# Breakout.net
KiCad netlist of a schematic drawn in EAGLE
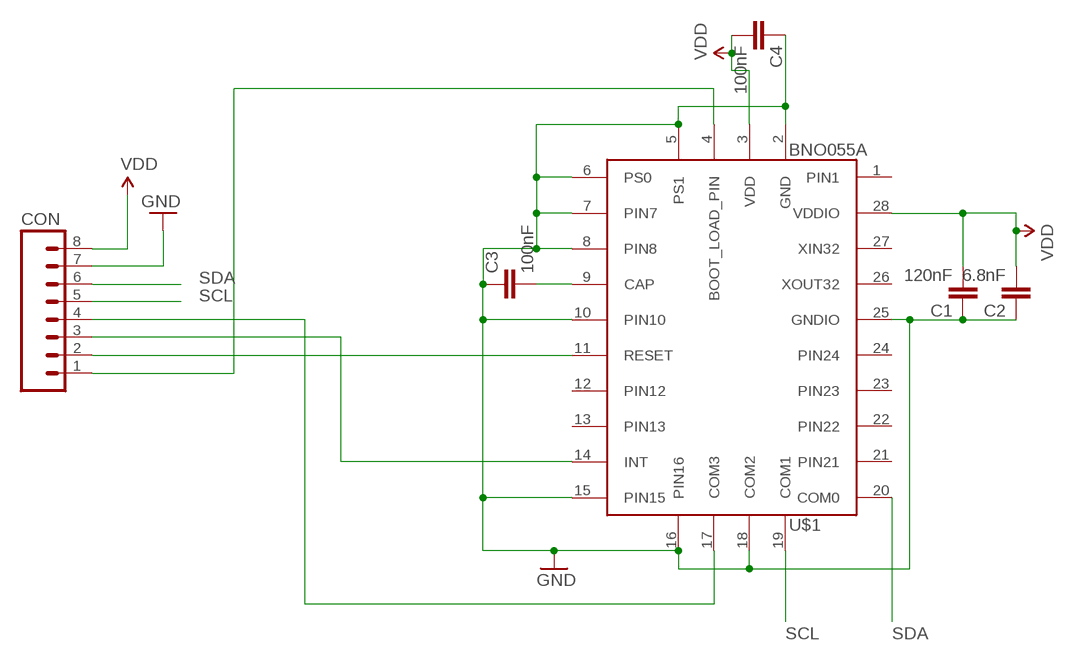
[diagram p0: schematic, sheet 1]

(export (version "E")
  (design (tool "Eeschema 10.0.6"))
  (components
    (comp (ref "C1")
      (value "120nF")
      (footprint "eagle-import:1206")
      (libsource (lib "eagle-import") (part "CAP1206"))
    )
    (comp (ref "C2")
      (value "6.8nF")
      (footprint "eagle-import:1206")
      (libsource (lib "eagle-import") (part "CAP1206"))
    )
    (comp (ref "C3")
      (value "100nF")
      (footprint "eagle-import:1206")
      (libsource (lib "eagle-import") (part "CAP1206"))
    )
    (comp (ref "C4")
      (value "100nF")
      (footprint "eagle-import:1206")
      (libsource (lib "eagle-import") (part "CAP1206"))
    )
    (comp (ref "CON")
      (value "M08NO_SILK")
      (footprint "eagle-import:1X08_NO_SILK")
      (libsource (lib "eagle-import") (part "M08NO_SILK"))
    )
    (comp (ref "U$1")
      (value "BNO055A")
      (footprint "eagle-import:BNO055")
      (libsource (lib "eagle-import") (part "BNO055A"))
    )
  )
  (nets
    (net (code "1") (name "/SCL") (class "Default")
      (node (ref "CON") (pin "5") (pinfunction "5_5") (pintype "passive"))
      (node (ref "U$1") (pin "19") (pinfunction "COM1_19") (pintype "bidirectional"))
    )
    (net (code "2") (name "/SDA") (class "Default")
      (node (ref "CON") (pin "6") (pinfunction "6_6") (pintype "passive"))
      (node (ref "U$1") (pin "20") (pinfunction "COM0_20") (pintype "bidirectional"))
    )
    (net (code "3") (name "GND") (class "Default")
      (node (ref "C1") (pin "1") (pinfunction "1_1") (pintype "passive"))
      (node (ref "C2") (pin "1") (pinfunction "1_1") (pintype "passive"))
      (node (ref "C3") (pin "1") (pinfunction "1_1") (pintype "passive"))
      (node (ref "C4") (pin "1") (pinfunction "1_1") (pintype "passive"))
      (node (ref "CON") (pin "7") (pinfunction "7_7") (pintype "passive"))
      (node (ref "U$1") (pin "10") (pinfunction "PIN10_10") (pintype "bidirectional"))
      (node (ref "U$1") (pin "15") (pinfunction "PIN15_15") (pintype "bidirectional"))
      (node (ref "U$1") (pin "16") (pinfunction "PIN16_16") (pintype "bidirectional"))
      (node (ref "U$1") (pin "18") (pinfunction "COM2_18") (pintype "bidirectional"))
      (node (ref "U$1") (pin "2") (pinfunction "GND_2") (pintype "bidirectional"))
      (node (ref "U$1") (pin "25") (pinfunction "GNDIO_25") (pintype "bidirectional"))
      (node (ref "U$1") (pin "5") (pinfunction "PS1_5") (pintype "bidirectional"))
      (node (ref "U$1") (pin "6") (pinfunction "PS0_6") (pintype "bidirectional"))
      (node (ref "U$1") (pin "7") (pinfunction "PIN7_7") (pintype "bidirectional"))
      (node (ref "U$1") (pin "8") (pinfunction "PIN8_8") (pintype "bidirectional"))
    )
    (net (code "4") (name "Net-(U$1-BOOT_LOAD_PIN)") (class "Default")
      (node (ref "CON") (pin "1") (pinfunction "1_1") (pintype "passive"))
      (node (ref "U$1") (pin "4") (pinfunction "BOOT_LOAD_PIN_4") (pintype "bidirectional"))
    )
    (net (code "5") (name "Net-(U$1-CAP)") (class "Default")
      (node (ref "C3") (pin "2") (pinfunction "2_2") (pintype "passive"))
      (node (ref "U$1") (pin "9") (pinfunction "CAP_9") (pintype "bidirectional"))
    )
    (net (code "6") (name "Net-(U$1-COM3)") (class "Default")
      (node (ref "CON") (pin "4") (pinfunction "4_4") (pintype "passive"))
      (node (ref "U$1") (pin "17") (pinfunction "COM3_17") (pintype "bidirectional"))
    )
    (net (code "7") (name "Net-(U$1-INT)") (class "Default")
      (node (ref "CON") (pin "3") (pinfunction "3_3") (pintype "passive"))
      (node (ref "U$1") (pin "14") (pinfunction "INT_14") (pintype "bidirectional"))
    )
    (net (code "8") (name "Net-(U$1-RESET)") (class "Default")
      (node (ref "CON") (pin "2") (pinfunction "2_2") (pintype "passive"))
      (node (ref "U$1") (pin "11") (pinfunction "RESET_11") (pintype "bidirectional"))
    )
    (net (code "9") (name "VDD") (class "Default")
      (node (ref "C1") (pin "2") (pinfunction "2_2") (pintype "passive"))
      (node (ref "C2") (pin "2") (pinfunction "2_2") (pintype "passive"))
      (node (ref "C4") (pin "2") (pinfunction "2_2") (pintype "passive"))
      (node (ref "CON") (pin "8") (pinfunction "8_8") (pintype "passive"))
      (node (ref "U$1") (pin "28") (pinfunction "VDDIO_28") (pintype "bidirectional"))
      (node (ref "U$1") (pin "3") (pinfunction "VDD_3") (pintype "bidirectional"))
    )
    (net (code "10") (name "unconnected-(U$1-PIN1-Pad1)") (class "Default")
      (node (ref "U$1") (pin "1") (pinfunction "PIN1_1") (pintype "bidirectional"))
    )
    (net (code "11") (name "unconnected-(U$1-PIN12-Pad12)") (class "Default")
      (node (ref "U$1") (pin "12") (pinfunction "PIN12_12") (pintype "bidirectional"))
    )
    (net (code "12") (name "unconnected-(U$1-PIN13-Pad13)") (class "Default")
      (node (ref "U$1") (pin "13") (pinfunction "PIN13_13") (pintype "bidirectional"))
    )
    (net (code "13") (name "unconnected-(U$1-PIN21-Pad21)") (class "Default")
      (node (ref "U$1") (pin "21") (pinfunction "PIN21_21") (pintype "bidirectional"))
    )
    (net (code "14") (name "unconnected-(U$1-PIN22-Pad22)") (class "Default")
      (node (ref "U$1") (pin "22") (pinfunction "PIN22_22") (pintype "bidirectional"))
    )
    (net (code "15") (name "unconnected-(U$1-PIN23-Pad23)") (class "Default")
      (node (ref "U$1") (pin "23") (pinfunction "PIN23_23") (pintype "bidirectional"))
    )
    (net (code "16") (name "unconnected-(U$1-PIN24-Pad24)") (class "Default")
      (node (ref "U$1") (pin "24") (pinfunction "PIN24_24") (pintype "bidirectional"))
    )
    (net (code "17") (name "unconnected-(U$1-XIN32-Pad27)") (class "Default")
      (node (ref "U$1") (pin "27") (pinfunction "XIN32_27") (pintype "bidirectional"))
    )
    (net (code "18") (name "unconnected-(U$1-XOUT32-Pad26)") (class "Default")
      (node (ref "U$1") (pin "26") (pinfunction "XOUT32_26") (pintype "bidirectional"))
    )
  )
)
